# 05_kbd_pm.net
KiCad netlist of a schematic drawn in Altium Designer
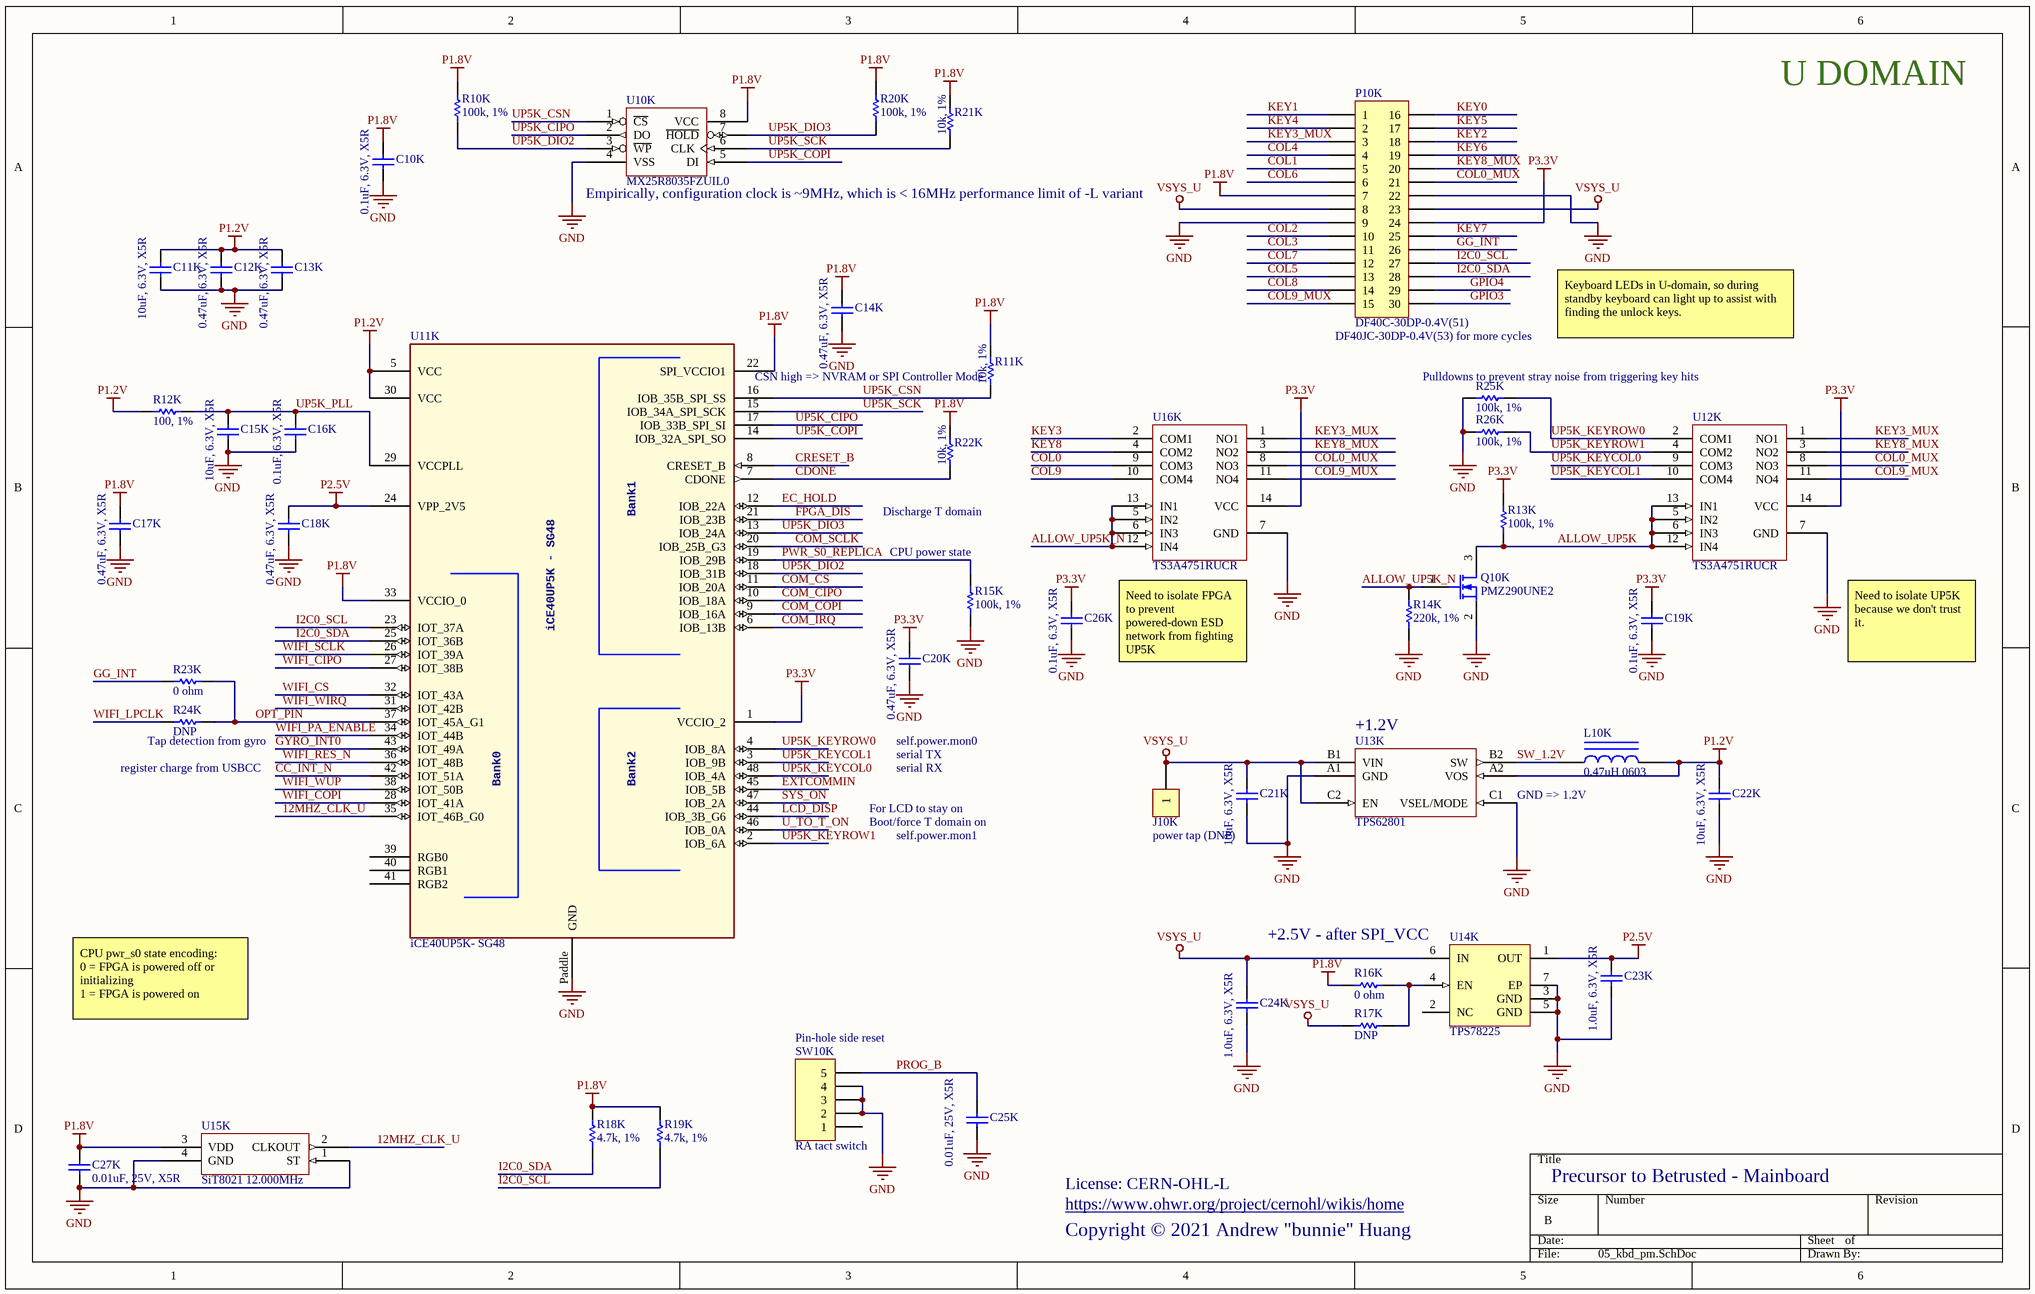
[diagram p0: 05_kbd_pm.SchDoc]

(export (version "E")
  (design (tool "Eeschema 10.0.6"))
  (components
    (comp (ref "C10K")
      (value "0.1uF, 6.3V, X5R")
      (footprint "B_CAP0201")
      (description "Capacitor (Semiconductor SIM Model)")
      (fields (field (name "MPN") "CL03A104KQ3NNNC"))
      (libsource (lib "Miscellaneous Devices") (part "Cap Semi"))
    )
    (comp (ref "C11K")
      (value "10uF, 6.3V, X5R")
      (footprint "B_CAP0603")
      (description "Capacitor (Semiconductor SIM Model)")
      (fields (field (name "MPN") "CL10A106MQ8NNNC"))
      (libsource (lib "Miscellaneous Devices") (part "Cap Semi"))
    )
    (comp (ref "C12K")
      (value "0.47uF, 6.3V, X5R")
      (footprint "B_CAP0201")
      (description "Capacitor (Semiconductor SIM Model)")
      (fields (field (name "MPN") "CL03A474KQ3NNNH"))
      (libsource (lib "Miscellaneous Devices") (part "Cap Semi"))
    )
    (comp (ref "C13K")
      (value "0.47uF, 6.3V, X5R")
      (footprint "B_CAP0201")
      (description "Capacitor (Semiconductor SIM Model)")
      (fields (field (name "MPN") "CL03A474KQ3NNNH"))
      (libsource (lib "Miscellaneous Devices") (part "Cap Semi"))
    )
    (comp (ref "C14K")
      (value "0.47uF, 6.3V, X5R")
      (footprint "B_CAP0201")
      (description "Capacitor (Semiconductor SIM Model)")
      (fields (field (name "MPN") "CL03A474KQ3NNNH"))
      (libsource (lib "Miscellaneous Devices") (part "Cap Semi"))
    )
    (comp (ref "C15K")
      (value "10uF, 6.3V, X5R")
      (footprint "B_CAP0603")
      (description "Capacitor (Semiconductor SIM Model)")
      (fields (field (name "MPN") "CL10A106MQ8NNNC"))
      (libsource (lib "Miscellaneous Devices") (part "Cap Semi"))
    )
    (comp (ref "C16K")
      (value "0.1uF, 6.3V, X5R")
      (footprint "B_CAP0201")
      (description "Capacitor (Semiconductor SIM Model)")
      (fields (field (name "MPN") "CL03A104KQ3NNNC"))
      (libsource (lib "Miscellaneous Devices") (part "Cap Semi"))
    )
    (comp (ref "C17K")
      (value "0.47uF, 6.3V, X5R")
      (footprint "B_CAP0201")
      (description "Capacitor (Semiconductor SIM Model)")
      (fields (field (name "MPN") "CL03A474KQ3NNNH"))
      (libsource (lib "Miscellaneous Devices") (part "Cap Semi"))
    )
    (comp (ref "C18K")
      (value "0.47uF, 6.3V, X5R")
      (footprint "B_CAP0201")
      (description "Capacitor (Semiconductor SIM Model)")
      (fields (field (name "MPN") "CL03A474KQ3NNNH"))
      (libsource (lib "Miscellaneous Devices") (part "Cap Semi"))
    )
    (comp (ref "C19K")
      (value "0.1uF, 6.3V, X5R")
      (footprint "B_CAP0201")
      (description "Capacitor (Semiconductor SIM Model)")
      (fields (field (name "MPN") "CL03A104KQ3NNNC"))
      (libsource (lib "Miscellaneous Devices") (part "Cap Semi"))
    )
    (comp (ref "C20K")
      (value "0.47uF, 6.3V, X5R")
      (footprint "B_CAP0201")
      (description "Capacitor (Semiconductor SIM Model)")
      (fields (field (name "MPN") "CL03A474KQ3NNNH"))
      (libsource (lib "Miscellaneous Devices") (part "Cap Semi"))
    )
    (comp (ref "C21K")
      (value "10uF, 6.3V, X5R")
      (footprint "B_CAP0603")
      (description "Capacitor (Semiconductor SIM Model)")
      (fields (field (name "MPN") "CL10A106MQ8NNNC"))
      (libsource (lib "Miscellaneous Devices") (part "Cap Semi"))
    )
    (comp (ref "C22K")
      (value "10uF, 6.3V, X5R")
      (footprint "B_CAP0603")
      (description "Capacitor (Semiconductor SIM Model)")
      (fields (field (name "MPN") "CL10A106MQ8NNNC"))
      (libsource (lib "Miscellaneous Devices") (part "Cap Semi"))
    )
    (comp (ref "C23K")
      (value "1.0uF, 6.3V, X5R")
      (footprint "B_CAP0201")
      (description "Capacitor (Semiconductor SIM Model)")
      (fields (field (name "MPN") "GRM033R60J105MEA2D"))
      (libsource (lib "Miscellaneous Devices") (part "Cap Semi"))
    )
    (comp (ref "C24K")
      (value "1.0uF, 6.3V, X5R")
      (footprint "B_CAP0201")
      (description "Capacitor (Semiconductor SIM Model)")
      (fields (field (name "MPN") "GRM033R60J105MEA2D"))
      (libsource (lib "Miscellaneous Devices") (part "Cap Semi"))
    )
    (comp (ref "C25K")
      (value "0.01uF, 25V, X5R")
      (footprint "B_RES0201")
      (description "Capacitor (Semiconductor SIM Model)")
      (fields (field (name "MPN") "GRM033R61E103KA12D"))
      (libsource (lib "Miscellaneous Devices") (part "Cap Semi"))
    )
    (comp (ref "C26K")
      (value "0.1uF, 6.3V, X5R")
      (footprint "B_CAP0201")
      (description "Capacitor (Semiconductor SIM Model)")
      (fields (field (name "MPN") "CL03A104KQ3NNNC"))
      (libsource (lib "Miscellaneous Devices") (part "Cap Semi"))
    )
    (comp (ref "C27K")
      (value "0.01uF, 25V, X5R")
      (footprint "B_RES0201")
      (description "Capacitor (Semiconductor SIM Model)")
      (fields (field (name "MPN") "GRM033R61E103KA12D"))
      (libsource (lib "Miscellaneous Devices") (part "Cap Semi"))
    )
    (comp (ref "J10K")
      (value "power tap (DNP)")
      (footprint "B_PWRTAP0402")
      (description "Connector")
      (fields (field (name "MPN") "DNP"))
      (libsource (lib "*") (part "CON1"))
    )
    (comp (ref "L10K")
      (value "0.47uH 0603")
      (footprint "B_IND0603")
      (description "Magnetic-Core Inductor")
      (fields (field (name "MPN") "TFM160808ALC-R47MTAA"))
      (libsource (lib "Miscellaneous Devices") (part "Inductor Iron"))
    )
    (comp (ref "P10K")
      (value "DF40C-30DP-0.4V(51)")
      (footprint "HRS_DF40C-30DP-0.4V(51)")
      (description "Header, 15-Pin, Dual row")
      (fields (field (name "PUBLISHER") "Altium Limited"))
      (libsource (lib "Miscellaneous Connectors") (part "Header 15X2A"))
    )
    (comp (ref "Q10K")
      (value "PMZ290UNE2")
      (footprint "SOT883")
      (description "N-Channel MOSFET")
      (fields (field (name "PUBLISHER") "Altium Limited"))
      (libsource (lib "Miscellaneous Devices") (part "MOSFET-N"))
    )
    (comp (ref "R10K")
      (value "100k, 1%")
      (footprint "B_RES0201")
      (description "Resistor")
      (fields (field (name "MPN") "ANY"))
      (libsource (lib "Miscellaneous Devices") (part "Res1"))
    )
    (comp (ref "R11K")
      (value "10k, 1%")
      (footprint "B_RES0201")
      (description "Resistor")
      (fields (field (name "MPN") "ANY"))
      (libsource (lib "Miscellaneous Devices") (part "Res1"))
    )
    (comp (ref "R12K")
      (value "100, 1%")
      (footprint "B_RES0402")
      (description "Resistor")
      (fields (field (name "MPN") "ANY"))
      (libsource (lib "Miscellaneous Devices") (part "Res1"))
    )
    (comp (ref "R13K")
      (value "100k, 1%")
      (footprint "B_RES0201")
      (description "Resistor")
      (fields (field (name "MPN") "ANY"))
      (libsource (lib "Miscellaneous Devices") (part "Res1"))
    )
    (comp (ref "R14K")
      (value "220k, 1%")
      (footprint "B_RES0201")
      (description "Resistor")
      (fields (field (name "MPN") "ANY"))
      (libsource (lib "Miscellaneous Devices") (part "Res1"))
    )
    (comp (ref "R15K")
      (value "100k, 1%")
      (footprint "B_RES0201")
      (description "Resistor")
      (fields (field (name "MPN") "ANY"))
      (libsource (lib "Miscellaneous Devices") (part "Res1"))
    )
    (comp (ref "R16K")
      (value "0 ohm")
      (footprint "B_RES0201")
      (description "Resistor")
      (fields (field (name "MPN") "ANY"))
      (libsource (lib "Miscellaneous Devices") (part "Res1"))
    )
    (comp (ref "R17K")
      (value "DNP")
      (footprint "B_RES0201")
      (description "Resistor")
      (fields (field (name "MPN") "ANY"))
      (libsource (lib "Miscellaneous Devices") (part "Res1"))
    )
    (comp (ref "R18K")
      (value "4.7k, 1%")
      (footprint "B_RES0201")
      (description "Resistor")
      (fields (field (name "MPN") "ANY"))
      (libsource (lib "Miscellaneous Devices") (part "Res1"))
    )
    (comp (ref "R19K")
      (value "4.7k, 1%")
      (footprint "B_RES0201")
      (description "Resistor")
      (fields (field (name "MPN") "ANY"))
      (libsource (lib "Miscellaneous Devices") (part "Res1"))
    )
    (comp (ref "R20K")
      (value "100k, 1%")
      (footprint "B_RES0201")
      (description "Resistor")
      (fields (field (name "MPN") "ANY"))
      (libsource (lib "Miscellaneous Devices") (part "Res1"))
    )
    (comp (ref "R21K")
      (value "10k, 1%")
      (footprint "B_RES0201")
      (description "Resistor")
      (fields (field (name "MPN") "ANY"))
      (libsource (lib "Miscellaneous Devices") (part "Res1"))
    )
    (comp (ref "R22K")
      (value "10k, 1%")
      (footprint "B_RES0201")
      (description "Resistor")
      (fields (field (name "MPN") "ANY"))
      (libsource (lib "Miscellaneous Devices") (part "Res1"))
    )
    (comp (ref "R23K")
      (value "0 ohm")
      (footprint "B_RES0201")
      (description "Resistor")
      (fields (field (name "MPN") "ANY"))
      (libsource (lib "Miscellaneous Devices") (part "Res1"))
    )
    (comp (ref "R24K")
      (value "DNP")
      (footprint "B_RES0201")
      (description "Resistor")
      (fields (field (name "MPN") "ANY"))
      (libsource (lib "Miscellaneous Devices") (part "Res1"))
    )
    (comp (ref "R25K")
      (value "100k, 1%")
      (footprint "B_RES0201")
      (description "Resistor")
      (fields (field (name "MPN") "ANY"))
      (libsource (lib "Miscellaneous Devices") (part "Res1"))
    )
    (comp (ref "R26K")
      (value "100k, 1%")
      (footprint "B_RES0201")
      (description "Resistor")
      (fields (field (name "MPN") "ANY"))
      (libsource (lib "Miscellaneous Devices") (part "Res1"))
    )
    (comp (ref "SW10K")
      (value "RA tact switch")
      (footprint "CK_KMS221GPLFS")
      (fields (field (name "MPN") "KMS221GPLFS") (field (name "PUBLISHER") "Altium Limited"))
      (libsource (lib "Miscellaneous Connectors") (part "Header 5"))
    )
    (comp (ref "U10K")
      (value "MX25R8035FZUIL0")
      (footprint "USON-8")
      (description "64Mbit SPI NOR FLASH")
      (libsource (lib "commonsch") (part "EN25P05-50GCP"))
    )
    (comp (ref "U11K")
      (value "iCE40UP5K- SG48")
      (footprint "UP5K_QFN127P600-8N")
      (fields (field (name "MPN") "ICE40UP5K-SG48I"))
      (libsource (lib "LATTICEPLDS_Library") (part "iCE40UP5K- SG48"))
    )
    (comp (ref "U12K")
      (value "TS3A4751RUCR")
      (footprint "QFN40P200X200X40-14L")
      (description "0.9 ohm low voltage, single supply, 4-channel SPST analog switch")
      (libsource (lib "commonsch-new") (part "TS3A4751RGYR"))
    )
    (comp (ref "U13K")
      (value "TPS62801")
      (footprint "BGA6C35P2X3_70X105X40_NSMD")
      (description "Buck regulator, 4MHz, 0.6A, 0.8V-1.55V, low Iq")
      (fields (field (name "MPN") "TPS62801YKAT"))
      (libsource (lib "altium-import") (part "root_0_TPS62801_"))
    )
    (comp (ref "U14K")
      (value "TPS78225")
      (footprint "TI-DRV6-1600X1000TP_V")
      (description "500nA Iq, 150mA LDO")
      (fields (field (name "MPN") "TPS78225DRVT"))
      (libsource (lib "TI-TPS78225-Q1DRV6-1600X1000TP") (part "TI-TPS78225-Q1DRV6-1600X1000TP"))
    )
    (comp (ref "U15K")
      (value "SiT8021 12.000MHz")
      (footprint "SiTIME_CSP")
      (description "1 to 26 MHz micropower oscillator")
      (fields (field (name "MPN") "SIT8021AI-J4-18S-12.000000E"))
      (libsource (lib "altium-import") (part "root_2_SiT8021_"))
    )
    (comp (ref "U16K")
      (value "TS3A4751RUCR")
      (footprint "QFN40P200X200X40-14L")
      (description "0.9 ohm low voltage, single supply, 4-channel SPST analog switch")
      (libsource (lib "commonsch-new") (part "TS3A4751RGYR"))
    )
  )
  (nets
    (net (code "1") (name "/12MHZ_CLK_U") (class "Default")
      (node (ref "U11K") (pin "35") (pinfunction "IOT_46B_G0_35") (pintype "bidirectional"))
      (node (ref "U15K") (pin "2") (pinfunction "CLKOUT_2") (pintype "output"))
    )
    (net (code "2") (name "/ALLOW_UP5K") (class "Default")
      (node (ref "Q10K") (pin "3") (pinfunction "D_3") (pintype "passive"))
      (node (ref "R13K") (pin "1") (pinfunction "1_1") (pintype "passive"))
      (node (ref "U12K") (pin "12") (pinfunction "IN4_12") (pintype "input"))
      (node (ref "U12K") (pin "13") (pinfunction "IN1_13") (pintype "input"))
      (node (ref "U12K") (pin "5") (pinfunction "IN2_5") (pintype "input"))
      (node (ref "U12K") (pin "6") (pinfunction "IN3_6") (pintype "input"))
    )
    (net (code "3") (name "/ALLOW_UP5K_N") (class "Default")
      (node (ref "Q10K") (pin "1") (pinfunction "G_1") (pintype "passive"))
      (node (ref "R14K") (pin "2") (pinfunction "2_2") (pintype "passive"))
      (node (ref "U16K") (pin "12") (pinfunction "IN4_12") (pintype "input"))
      (node (ref "U16K") (pin "13") (pinfunction "IN1_13") (pintype "input"))
      (node (ref "U16K") (pin "5") (pinfunction "IN2_5") (pintype "input"))
      (node (ref "U16K") (pin "6") (pinfunction "IN3_6") (pintype "input"))
    )
    (net (code "4") (name "/CC_INT_N") (class "Default")
      (node (ref "U11K") (pin "42") (pinfunction "IOT_51A_42") (pintype "bidirectional"))
    )
    (net (code "5") (name "/CDONE") (class "Default")
      (node (ref "R22K") (pin "2") (pinfunction "2_2") (pintype "passive"))
      (node (ref "U11K") (pin "7") (pinfunction "CDONE_7") (pintype "output"))
    )
    (net (code "6") (name "/COL0") (class "Default")
      (node (ref "U16K") (pin "9") (pinfunction "COM3_9") (pintype "passive"))
    )
    (net (code "7") (name "/COL0_MUX") (class "Default")
      (node (ref "P10K") (pin "21") (pinfunction "21_21") (pintype "passive"))
      (node (ref "U12K") (pin "8") (pinfunction "NO3_8") (pintype "passive"))
      (node (ref "U16K") (pin "8") (pinfunction "NO3_8") (pintype "passive"))
    )
    (net (code "8") (name "/COL1") (class "Default")
      (node (ref "P10K") (pin "5") (pinfunction "5_5") (pintype "passive"))
    )
    (net (code "9") (name "/COL2") (class "Default")
      (node (ref "P10K") (pin "10") (pinfunction "10_10") (pintype "passive"))
    )
    (net (code "10") (name "/COL3") (class "Default")
      (node (ref "P10K") (pin "11") (pinfunction "11_11") (pintype "passive"))
    )
    (net (code "11") (name "/COL4") (class "Default")
      (node (ref "P10K") (pin "4") (pinfunction "4_4") (pintype "passive"))
    )
    (net (code "12") (name "/COL5") (class "Default")
      (node (ref "P10K") (pin "13") (pinfunction "13_13") (pintype "passive"))
    )
    (net (code "13") (name "/COL6") (class "Default")
      (node (ref "P10K") (pin "6") (pinfunction "6_6") (pintype "passive"))
    )
    (net (code "14") (name "/COL7") (class "Default")
      (node (ref "P10K") (pin "12") (pinfunction "12_12") (pintype "passive"))
    )
    (net (code "15") (name "/COL8") (class "Default")
      (node (ref "P10K") (pin "14") (pinfunction "14_14") (pintype "passive"))
    )
    (net (code "16") (name "/COL9") (class "Default")
      (node (ref "U16K") (pin "10") (pinfunction "COM4_10") (pintype "passive"))
    )
    (net (code "17") (name "/COL9_MUX") (class "Default")
      (node (ref "P10K") (pin "15") (pinfunction "15_15") (pintype "passive"))
      (node (ref "U12K") (pin "11") (pinfunction "NO4_11") (pintype "passive"))
      (node (ref "U16K") (pin "11") (pinfunction "NO4_11") (pintype "passive"))
    )
    (net (code "18") (name "/COM_CIPO") (class "Default")
      (node (ref "U11K") (pin "10") (pinfunction "IOB_18A_10") (pintype "bidirectional"))
    )
    (net (code "19") (name "/COM_COPI") (class "Default")
      (node (ref "U11K") (pin "9") (pinfunction "IOB_16A_9") (pintype "bidirectional"))
    )
    (net (code "20") (name "/COM_CS") (class "Default")
      (node (ref "U11K") (pin "11") (pinfunction "IOB_20A_11") (pintype "bidirectional"))
    )
    (net (code "21") (name "/COM_IRQ") (class "Default")
      (node (ref "U11K") (pin "6") (pinfunction "IOB_13B_6") (pintype "bidirectional"))
    )
    (net (code "22") (name "/COM_SCLK") (class "Default")
      (node (ref "U11K") (pin "20") (pinfunction "IOB_25B_G3_20") (pintype "bidirectional"))
    )
    (net (code "23") (name "/CRESET_B") (class "Default")
      (node (ref "U11K") (pin "8") (pinfunction "CRESET_B_8") (pintype "input"))
    )
    (net (code "24") (name "/EC_HOLD") (class "Default")
      (node (ref "U11K") (pin "12") (pinfunction "IOB_22A_12") (pintype "bidirectional"))
    )
    (net (code "25") (name "/EXTCOMMIN") (class "Default")
      (node (ref "U11K") (pin "45") (pinfunction "IOB_5B_45") (pintype "bidirectional"))
    )
    (net (code "26") (name "/FPGA_DIS") (class "Default")
      (node (ref "U11K") (pin "21") (pinfunction "IOB_23B_21") (pintype "bidirectional"))
    )
    (net (code "27") (name "/GG_INT") (class "Default")
      (node (ref "P10K") (pin "26") (pinfunction "26_26") (pintype "passive"))
      (node (ref "R23K") (pin "1") (pinfunction "1_1") (pintype "passive"))
    )
    (net (code "28") (name "/GPIO3") (class "Default")
      (node (ref "P10K") (pin "30") (pinfunction "30_30") (pintype "passive"))
    )
    (net (code "29") (name "/GPIO4") (class "Default")
      (node (ref "P10K") (pin "29") (pinfunction "29_29") (pintype "passive"))
    )
    (net (code "30") (name "/GYRO_INT0") (class "Default")
      (node (ref "U11K") (pin "43") (pinfunction "IOT_49A_43") (pintype "bidirectional"))
    )
    (net (code "31") (name "/I2C0_SCL") (class "Default")
      (node (ref "P10K") (pin "27") (pinfunction "27_27") (pintype "passive"))
      (node (ref "R19K") (pin "1") (pinfunction "1_1") (pintype "passive"))
      (node (ref "U11K") (pin "23") (pinfunction "IOT_37A_23") (pintype "bidirectional"))
    )
    (net (code "32") (name "/I2C0_SDA") (class "Default")
      (node (ref "P10K") (pin "28") (pinfunction "28_28") (pintype "passive"))
      (node (ref "R18K") (pin "1") (pinfunction "1_1") (pintype "passive"))
      (node (ref "U11K") (pin "25") (pinfunction "IOT_36B_25") (pintype "bidirectional"))
    )
    (net (code "33") (name "/KEY0") (class "Default")
      (node (ref "P10K") (pin "16") (pinfunction "16_16") (pintype "passive"))
    )
    (net (code "34") (name "/KEY1") (class "Default")
      (node (ref "P10K") (pin "1") (pinfunction "1_1") (pintype "passive"))
    )
    (net (code "35") (name "/KEY2") (class "Default")
      (node (ref "P10K") (pin "18") (pinfunction "18_18") (pintype "passive"))
    )
    (net (code "36") (name "/KEY3") (class "Default")
      (node (ref "U16K") (pin "2") (pinfunction "COM1_2") (pintype "passive"))
    )
    (net (code "37") (name "/KEY3_MUX") (class "Default")
      (node (ref "P10K") (pin "3") (pinfunction "3_3") (pintype "passive"))
      (node (ref "U12K") (pin "1") (pinfunction "NO1_1") (pintype "passive"))
      (node (ref "U16K") (pin "1") (pinfunction "NO1_1") (pintype "passive"))
    )
    (net (code "38") (name "/KEY4") (class "Default")
      (node (ref "P10K") (pin "2") (pinfunction "2_2") (pintype "passive"))
    )
    (net (code "39") (name "/KEY5") (class "Default")
      (node (ref "P10K") (pin "17") (pinfunction "17_17") (pintype "passive"))
    )
    (net (code "40") (name "/KEY6") (class "Default")
      (node (ref "P10K") (pin "19") (pinfunction "19_19") (pintype "passive"))
    )
    (net (code "41") (name "/KEY7") (class "Default")
      (node (ref "P10K") (pin "25") (pinfunction "25_25") (pintype "passive"))
    )
    (net (code "42") (name "/KEY8") (class "Default")
      (node (ref "U16K") (pin "4") (pinfunction "COM2_4") (pintype "passive"))
    )
    (net (code "43") (name "/KEY8_MUX") (class "Default")
      (node (ref "P10K") (pin "20") (pinfunction "20_20") (pintype "passive"))
      (node (ref "U12K") (pin "3") (pinfunction "NO2_3") (pintype "passive"))
      (node (ref "U16K") (pin "3") (pinfunction "NO2_3") (pintype "passive"))
    )
    (net (code "44") (name "/LCD_DISP") (class "Default")
      (node (ref "U11K") (pin "44") (pinfunction "IOB_3B_G6_44") (pintype "bidirectional"))
    )
    (net (code "45") (name "/OPT_PIN") (class "Default")
      (node (ref "R23K") (pin "2") (pinfunction "2_2") (pintype "passive"))
      (node (ref "R24K") (pin "2") (pinfunction "2_2") (pintype "passive"))
      (node (ref "U11K") (pin "37") (pinfunction "IOT_45A_G1_37") (pintype "bidirectional"))
    )
    (net (code "46") (name "/PROG_B") (class "Default")
      (node (ref "C25K") (pin "1") (pinfunction "1_1") (pintype "passive"))
      (node (ref "SW10K") (pin "5") (pinfunction "5_5") (pintype "passive"))
    )
    (net (code "47") (name "/PWR_S0_REPLICA") (class "Default")
      (node (ref "R15K") (pin "2") (pinfunction "2_2") (pintype "passive"))
      (node (ref "U11K") (pin "19") (pinfunction "IOB_29B_19") (pintype "bidirectional"))
    )
    (net (code "48") (name "/SW_1.2V") (class "Default")
      (node (ref "L10K") (pin "1") (pinfunction "1_1") (pintype "passive"))
      (node (ref "U13K") (pin "B2") (pinfunction "SW_B2") (pintype "output"))
    )
    (net (code "49") (name "/SYS_ON") (class "Default")
      (node (ref "U11K") (pin "47") (pinfunction "IOB_2A_47") (pintype "bidirectional"))
    )
    (net (code "50") (name "/UP5K_CIPO") (class "Default")
      (node (ref "U10K") (pin "2") (pinfunction "DO_2") (pintype "output"))
      (node (ref "U11K") (pin "17") (pinfunction "IOB_33B_SPI_SI_17") (pintype "passive"))
    )
    (net (code "51") (name "/UP5K_COPI") (class "Default")
      (node (ref "U10K") (pin "5") (pinfunction "DI_5") (pintype "input"))
      (node (ref "U11K") (pin "14") (pinfunction "IOB_32A_SPI_SO_14") (pintype "passive"))
    )
    (net (code "52") (name "/UP5K_CSN") (class "Default")
      (node (ref "R11K") (pin "2") (pinfunction "2_2") (pintype "passive"))
      (node (ref "U10K") (pin "1") (pinfunction "~{CS}_1") (pintype "input"))
      (node (ref "U11K") (pin "16") (pinfunction "IOB_35B_SPI_SS_16") (pintype "passive"))
    )
    (net (code "53") (name "/UP5K_DIO2") (class "Default")
      (node (ref "R10K") (pin "1") (pinfunction "1_1") (pintype "passive"))
      (node (ref "U10K") (pin "3") (pinfunction "~{WP}_3") (pintype "input"))
      (node (ref "U11K") (pin "18") (pinfunction "IOB_31B_18") (pintype "bidirectional"))
    )
    (net (code "54") (name "/UP5K_DIO3") (class "Default")
      (node (ref "R20K") (pin "1") (pinfunction "1_1") (pintype "passive"))
      (node (ref "U10K") (pin "7") (pinfunction "~{HOLD}_7") (pintype "bidirectional"))
      (node (ref "U11K") (pin "13") (pinfunction "IOB_24A_13") (pintype "bidirectional"))
    )
    (net (code "55") (name "/UP5K_KEYCOL0") (class "Default")
      (node (ref "U11K") (pin "48") (pinfunction "IOB_4A_48") (pintype "bidirectional"))
      (node (ref "U12K") (pin "9") (pinfunction "COM3_9") (pintype "passive"))
    )
    (net (code "56") (name "/UP5K_KEYCOL1") (class "Default")
      (node (ref "U11K") (pin "3") (pinfunction "IOB_9B_3") (pintype "bidirectional"))
      (node (ref "U12K") (pin "10") (pinfunction "COM4_10") (pintype "passive"))
    )
    (net (code "57") (name "/UP5K_KEYROW0") (class "Default")
      (node (ref "R25K") (pin "1") (pinfunction "1_1") (pintype "passive"))
      (node (ref "U11K") (pin "4") (pinfunction "IOB_8A_4") (pintype "bidirectional"))
      (node (ref "U12K") (pin "2") (pinfunction "COM1_2") (pintype "passive"))
    )
    (net (code "58") (name "/UP5K_KEYROW1") (class "Default")
      (node (ref "R26K") (pin "1") (pinfunction "1_1") (pintype "passive"))
      (node (ref "U11K") (pin "2") (pinfunction "IOB_6A_2") (pintype "bidirectional"))
      (node (ref "U12K") (pin "4") (pinfunction "COM2_4") (pintype "passive"))
    )
    (net (code "59") (name "/UP5K_PLL") (class "Default")
      (node (ref "C15K") (pin "1") (pinfunction "1_1") (pintype "passive"))
      (node (ref "C16K") (pin "1") (pinfunction "1_1") (pintype "passive"))
      (node (ref "R12K") (pin "1") (pinfunction "1_1") (pintype "passive"))
      (node (ref "U11K") (pin "29") (pinfunction "VCCPLL_29") (pintype "power_in"))
    )
    (net (code "60") (name "/UP5K_SCK") (class "Default")
      (node (ref "R21K") (pin "2") (pinfunction "2_2") (pintype "passive"))
      (node (ref "U10K") (pin "6") (pinfunction "CLK_6") (pintype "input"))
      (node (ref "U11K") (pin "15") (pinfunction "IOB_34A_SPI_SCK_15") (pintype "passive"))
    )
    (net (code "61") (name "/U_TO_T_ON") (class "Default")
      (node (ref "U11K") (pin "46") (pinfunction "IOB_0A_46") (pintype "bidirectional"))
    )
    (net (code "62") (name "/WIFI_CIPO") (class "Default")
      (node (ref "U11K") (pin "27") (pinfunction "IOT_38B_27") (pintype "bidirectional"))
    )
    (net (code "63") (name "/WIFI_COPI") (class "Default")
      (node (ref "U11K") (pin "28") (pinfunction "IOT_41A_28") (pintype "bidirectional"))
    )
    (net (code "64") (name "/WIFI_CS") (class "Default")
      (node (ref "U11K") (pin "32") (pinfunction "IOT_43A_32") (pintype "bidirectional"))
    )
    (net (code "65") (name "/WIFI_LPCLK") (class "Default")
      (node (ref "R24K") (pin "1") (pinfunction "1_1") (pintype "passive"))
    )
    (net (code "66") (name "/WIFI_PA_ENABLE") (class "Default")
      (node (ref "U11K") (pin "34") (pinfunction "IOT_44B_34") (pintype "bidirectional"))
    )
    (net (code "67") (name "/WIFI_RES_N") (class "Default")
      (node (ref "U11K") (pin "36") (pinfunction "IOT_48B_36") (pintype "bidirectional"))
    )
    (net (code "68") (name "/WIFI_SCLK") (class "Default")
      (node (ref "U11K") (pin "26") (pinfunction "IOT_39A_26") (pintype "bidirectional"))
    )
    (net (code "69") (name "/WIFI_WIRQ") (class "Default")
      (node (ref "U11K") (pin "31") (pinfunction "IOT_42B_31") (pintype "bidirectional"))
    )
    (net (code "70") (name "/WIFI_WUP") (class "Default")
      (node (ref "U11K") (pin "38") (pinfunction "IOT_50B_38") (pintype "bidirectional"))
    )
    (net (code "71") (name "GND") (class "Default")
      (node (ref "C10K") (pin "2") (pinfunction "2_2") (pintype "passive"))
      (node (ref "C11K") (pin "2") (pinfunction "2_2") (pintype "passive"))
      (node (ref "C12K") (pin "2") (pinfunction "2_2") (pintype "passive"))
      (node (ref "C13K") (pin "2") (pinfunction "2_2") (pintype "passive"))
      (node (ref "C14K") (pin "2") (pinfunction "2_2") (pintype "passive"))
      (node (ref "C15K") (pin "2") (pinfunction "2_2") (pintype "passive"))
      (node (ref "C16K") (pin "2") (pinfunction "2_2") (pintype "passive"))
      (node (ref "C17K") (pin "2") (pinfunction "2_2") (pintype "passive"))
      (node (ref "C18K") (pin "2") (pinfunction "2_2") (pintype "passive"))
      (node (ref "C19K") (pin "2") (pinfunction "2_2") (pintype "passive"))
      (node (ref "C20K") (pin "2") (pinfunction "2_2") (pintype "passive"))
      (node (ref "C21K") (pin "2") (pinfunction "2_2") (pintype "passive"))
      (node (ref "C22K") (pin "2") (pinfunction "2_2") (pintype "passive"))
      (node (ref "C23K") (pin "2") (pinfunction "2_2") (pintype "passive"))
      (node (ref "C24K") (pin "2") (pinfunction "2_2") (pintype "passive"))
      (node (ref "C25K") (pin "2") (pinfunction "2_2") (pintype "passive"))
      (node (ref "C26K") (pin "2") (pinfunction "2_2") (pintype "passive"))
      (node (ref "C27K") (pin "2") (pinfunction "2_2") (pintype "passive"))
      (node (ref "P10K") (pin "22") (pinfunction "22_22") (pintype "passive"))
      (node (ref "P10K") (pin "9") (pinfunction "9_9") (pintype "passive"))
      (node (ref "Q10K") (pin "2") (pinfunction "S_2") (pintype "passive"))
      (node (ref "R14K") (pin "1") (pinfunction "1_1") (pintype "passive"))
      (node (ref "R15K") (pin "1") (pinfunction "1_1") (pintype "passive"))
      (node (ref "R25K") (pin "2") (pinfunction "2_2") (pintype "passive"))
      (node (ref "R26K") (pin "2") (pinfunction "2_2") (pintype "passive"))
      (node (ref "SW10K") (pin "2") (pinfunction "2_2") (pintype "passive"))
      (node (ref "SW10K") (pin "3") (pinfunction "3_3") (pintype "passive"))
      (node (ref "SW10K") (pin "4") (pinfunction "4_4") (pintype "passive"))
      (node (ref "U10K") (pin "4") (pinfunction "VSS_4") (pintype "power_in"))
      (node (ref "U11K") (pin "Paddle") (pinfunction "GND_Paddle") (pintype "power_in"))
      (node (ref "U12K") (pin "7") (pinfunction "GND_7") (pintype "power_in"))
      (node (ref "U13K") (pin "A1") (pinfunction "GND_A1") (pintype "power_in"))
      (node (ref "U13K") (pin "C1") (pinfunction "VSEL/MODE_C1") (pintype "input"))
      (node (ref "U14K") (pin "3") (pinfunction "GND_3") (pintype "power_in"))
      (node (ref "U14K") (pin "5") (pinfunction "GND_5") (pintype "power_in"))
      (node (ref "U14K") (pin "7") (pinfunction "EP_7") (pintype "power_in"))
      (node (ref "U15K") (pin "1") (pinfunction "ST_1") (pintype "input"))
      (node (ref "U15K") (pin "4") (pinfunction "GND_4") (pintype "power_in"))
      (node (ref "U16K") (pin "7") (pinfunction "GND_7") (pintype "power_in"))
    )
    (net (code "72") (name "Net-(U14K-EN)") (class "Default")
      (node (ref "R16K") (pin "2") (pinfunction "2_2") (pintype "passive"))
      (node (ref "R17K") (pin "2") (pinfunction "2_2") (pintype "passive"))
      (node (ref "U14K") (pin "4") (pinfunction "EN_4") (pintype "input"))
    )
    (net (code "73") (name "P1.2V") (class "Default")
      (node (ref "C11K") (pin "1") (pinfunction "1_1") (pintype "passive"))
      (node (ref "C12K") (pin "1") (pinfunction "1_1") (pintype "passive"))
      (node (ref "C13K") (pin "1") (pinfunction "1_1") (pintype "passive"))
      (node (ref "C22K") (pin "1") (pinfunction "1_1") (pintype "passive"))
      (node (ref "L10K") (pin "2") (pinfunction "2_2") (pintype "passive"))
      (node (ref "R12K") (pin "2") (pinfunction "2_2") (pintype "passive"))
      (node (ref "U11K") (pin "30") (pinfunction "VCC_30") (pintype "power_in"))
      (node (ref "U11K") (pin "5") (pinfunction "VCC_5") (pintype "power_in"))
      (node (ref "U13K") (pin "A2") (pinfunction "VOS_A2") (pintype "input"))
    )
    (net (code "74") (name "P1.8V") (class "Default")
      (node (ref "C10K") (pin "1") (pinfunction "1_1") (pintype "passive"))
      (node (ref "C14K") (pin "1") (pinfunction "1_1") (pintype "passive"))
      (node (ref "C17K") (pin "1") (pinfunction "1_1") (pintype "passive"))
      (node (ref "C27K") (pin "1") (pinfunction "1_1") (pintype "passive"))
      (node (ref "P10K") (pin "7") (pinfunction "7_7") (pintype "passive"))
      (node (ref "R10K") (pin "2") (pinfunction "2_2") (pintype "passive"))
      (node (ref "R11K") (pin "1") (pinfunction "1_1") (pintype "passive"))
      (node (ref "R16K") (pin "1") (pinfunction "1_1") (pintype "passive"))
      (node (ref "R18K") (pin "2") (pinfunction "2_2") (pintype "passive"))
      (node (ref "R19K") (pin "2") (pinfunction "2_2") (pintype "passive"))
      (node (ref "R20K") (pin "2") (pinfunction "2_2") (pintype "passive"))
      (node (ref "R21K") (pin "1") (pinfunction "1_1") (pintype "passive"))
      (node (ref "R22K") (pin "1") (pinfunction "1_1") (pintype "passive"))
      (node (ref "U10K") (pin "8") (pinfunction "VCC_8") (pintype "power_in"))
      (node (ref "U11K") (pin "22") (pinfunction "SPI_VCCIO1_22") (pintype "power_in"))
      (node (ref "U11K") (pin "33") (pinfunction "VCCIO_0_33") (pintype "power_in"))
      (node (ref "U15K") (pin "3") (pinfunction "VDD_3") (pintype "power_in"))
    )
    (net (code "75") (name "P2.5V") (class "Default")
      (node (ref "C18K") (pin "1") (pinfunction "1_1") (pintype "passive"))
      (node (ref "C23K") (pin "1") (pinfunction "1_1") (pintype "passive"))
      (node (ref "U11K") (pin "24") (pinfunction "VPP_2V5_24") (pintype "power_in"))
      (node (ref "U14K") (pin "1") (pinfunction "OUT_1") (pintype "power_in"))
    )
    (net (code "76") (name "P3.3V") (class "Default")
      (node (ref "C19K") (pin "1") (pinfunction "1_1") (pintype "passive"))
      (node (ref "C20K") (pin "1") (pinfunction "1_1") (pintype "passive"))
      (node (ref "C26K") (pin "1") (pinfunction "1_1") (pintype "passive"))
      (node (ref "P10K") (pin "24") (pinfunction "24_24") (pintype "passive"))
      (node (ref "R13K") (pin "2") (pinfunction "2_2") (pintype "passive"))
      (node (ref "U11K") (pin "1") (pinfunction "VCCIO_2_1") (pintype "power_in"))
      (node (ref "U12K") (pin "14") (pinfunction "VCC_14") (pintype "power_in"))
      (node (ref "U16K") (pin "14") (pinfunction "VCC_14") (pintype "power_in"))
    )
    (net (code "77") (name "VSYS_U") (class "Default")
      (node (ref "C21K") (pin "1") (pinfunction "1_1") (pintype "passive"))
      (node (ref "C24K") (pin "1") (pinfunction "1_1") (pintype "passive"))
      (node (ref "J10K") (pin "1") (pinfunction "1_1") (pintype "passive"))
      (node (ref "P10K") (pin "23") (pinfunction "23_23") (pintype "passive"))
      (node (ref "P10K") (pin "8") (pinfunction "8_8") (pintype "passive"))
      (node (ref "R17K") (pin "1") (pinfunction "1_1") (pintype "passive"))
      (node (ref "U13K") (pin "B1") (pinfunction "VIN_B1") (pintype "power_in"))
      (node (ref "U13K") (pin "C2") (pinfunction "EN_C2") (pintype "input"))
      (node (ref "U14K") (pin "6") (pinfunction "IN_6") (pintype "power_in"))
    )
    (net (code "78") (name "unconnected-(SW10K-Pad1)") (class "Default")
      (node (ref "SW10K") (pin "1") (pinfunction "1_1") (pintype "passive"))
    )
    (net (code "79") (name "unconnected-(U11K-RGB0-Pad39)") (class "Default")
      (node (ref "U11K") (pin "39") (pinfunction "RGB0_39") (pintype "open_collector"))
    )
    (net (code "80") (name "unconnected-(U11K-RGB1-Pad40)") (class "Default")
      (node (ref "U11K") (pin "40") (pinfunction "RGB1_40") (pintype "open_collector"))
    )
    (net (code "81") (name "unconnected-(U11K-RGB2-Pad41)") (class "Default")
      (node (ref "U11K") (pin "41") (pinfunction "RGB2_41") (pintype "open_collector"))
    )
    (net (code "82") (name "unconnected-(U14K-NC-Pad2)") (class "Default")
      (node (ref "U14K") (pin "2") (pinfunction "NC_2") (pintype "passive"))
    )
  )
)
